# Battery_manegment.net
KiCad netlist of a schematic drawn in Altium Designer
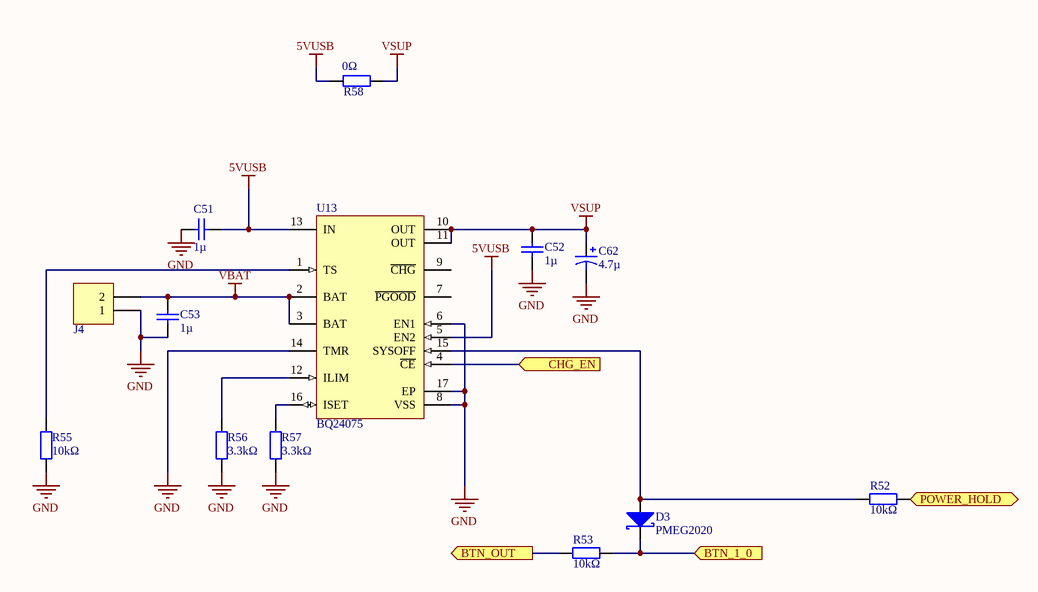
[diagram p0: Battery_manegment.SchDoc]

(export (version "E")
  (design (tool "Eeschema 10.0.6"))
  (components
    (comp (ref "C51")
      (value "1µ")
      (footprint "0603C")
      (description "ceramic X5R SMD capacitor smd 0603 1µF 50V")
      (fields (field (name "PART NUMBER") "ZSC0003") (field (name "MANUFACTURER") "Murata"))
      (libsource (lib "components") (part "Capacitor"))
    )
    (comp (ref "C52")
      (value "1µ")
      (footprint "0603C")
      (description "ceramic X5R SMD capacitor smd 0603 1µF 50V")
      (fields (field (name "PART NUMBER") "ZSC0003") (field (name "MANUFACTURER") "Murata"))
      (libsource (lib "components") (part "Capacitor"))
    )
    (comp (ref "C53")
      (value "1µ")
      (footprint "0603C")
      (description "ceramic X5R SMD capacitor smd 0603 1µF 50V")
      (fields (field (name "PART NUMBER") "ZSC0003") (field (name "MANUFACTURER") "Murata"))
      (libsource (lib "components") (part "Capacitor"))
    )
    (comp (ref "C62")
      (value "4.7µ")
      (footprint "A")
      (description "tantalum SMD capacitor 4.7µF 16V A case")
      (fields (field (name "PART NUMBER") "CST0011") (field (name "MANUFACTURER") "Kemet"))
      (libsource (lib "components") (part "Capacitor polarized"))
    )
    (comp (ref "D3")
      (value "PMEG2020")
      (footprint "SOD323")
      (description "Shotkey diode 2A 20V")
      (fields (field (name "PART NUMBER") "XDS0004") (field (name "MANUFACTURER") "Infineon"))
      (libsource (lib "components") (part "SCHOTTKY1"))
    )
    (comp (ref "J4")
      (value "B2B-PH-K-S(LF)(SN)")
      (footprint "JST_PH_2_V")
      (description "JST PH connector 2 poles vertical")
      (fields (field (name "PART NUMBER") "CJP0005") (field (name "MANUFACTURER") "JST"))
      (libsource (lib "components") (part "PH_2"))
    )
    (comp (ref "R52")
      (value "10kΩ")
      (footprint "0603R")
      (description "resistor smd 0603 10kΩ 1% 0.1w")
      (fields (field (name "PART NUMBER") "YRS0016") (field (name "MANUFACTURER") "Vishay"))
      (libsource (lib "components") (part "Resistor"))
    )
    (comp (ref "R53")
      (value "10kΩ")
      (footprint "0603R")
      (description "resistor smd 0603 10kΩ 1% 0.1w")
      (fields (field (name "PART NUMBER") "YRS0016") (field (name "MANUFACTURER") "Vishay"))
      (libsource (lib "components") (part "Resistor"))
    )
    (comp (ref "R55")
      (value "10kΩ")
      (footprint "0603R")
      (description "resistor smd 0603 10kΩ 1% 0.1w")
      (fields (field (name "PART NUMBER") "YRS0016") (field (name "MANUFACTURER") "Vishay"))
      (libsource (lib "") (part "Resistor_1"))
    )
    (comp (ref "R56")
      (value "3.3kΩ")
      (footprint "0603R")
      (description "resistor smd 0603 3.3kΩ 5% 0.1w")
      (fields (field (name "PART NUMBER") "XRS0055") (field (name "MANUFACTURER") "Yageo"))
      (libsource (lib "") (part "Resistor_1"))
    )
    (comp (ref "R57")
      (value "3.3kΩ")
      (footprint "0603R")
      (description "resistor smd 0603 3.3kΩ 5% 0.1w")
      (fields (field (name "PART NUMBER") "XRS0055") (field (name "MANUFACTURER") "Yageo"))
      (libsource (lib "") (part "Resistor_1"))
    )
    (comp (ref "R58")
      (value "0Ω")
      (footprint "0603R")
      (description "resistor smd 0603 0Ω 5% 0.1w")
      (fields (field (name "PART NUMBER") "XRS0022") (field (name "MANUFACTURER") "Panasonic"))
      (libsource (lib "") (part "Resistor_2"))
    )
    (comp (ref "U13")
      (value "BQ24075")
      (footprint "QFN16_PAD")
      (description "1.5-A USB-Friendly Li-Ion Battery Charger and Power-Path Management IC")
      (fields (field (name "PART NUMBER") "BAC0000") (field (name "MANUFACTURER") "Texas Instruments"))
      (libsource (lib "components") (part "BQ24075"))
    )
  )
  (nets
    (net (code "1") (name "/BTN_1_0") (class "Default")
      (node (ref "D3") (pin "2") (pinfunction "K_2") (pintype "passive"))
      (node (ref "R53") (pin "1") (pinfunction "1_1") (pintype "passive"))
    )
    (net (code "2") (name "/BTN_OUT") (class "Default")
      (node (ref "R53") (pin "2") (pinfunction "2_2") (pintype "passive"))
    )
    (net (code "3") (name "/CHG_EN") (class "Default")
      (node (ref "U13") (pin "4") (pinfunction "~{CE}_4") (pintype "input"))
    )
    (net (code "4") (name "/POWER_HOLD") (class "Default")
      (node (ref "R52") (pin "1") (pinfunction "1_1") (pintype "passive"))
    )
    (net (code "5") (name "5VUSB") (class "Default")
      (node (ref "C51") (pin "2") (pinfunction "2_2") (pintype "passive"))
      (node (ref "R58") (pin "1") (pinfunction "1_1") (pintype "passive"))
      (node (ref "U13") (pin "13") (pinfunction "IN_13") (pintype "power_in"))
      (node (ref "U13") (pin "5") (pinfunction "EN2_5") (pintype "input"))
    )
    (net (code "6") (name "GND") (class "Default")
      (node (ref "C51") (pin "1") (pinfunction "1_1") (pintype "passive"))
      (node (ref "C52") (pin "1") (pinfunction "1_1") (pintype "passive"))
      (node (ref "C53") (pin "1") (pinfunction "1_1") (pintype "passive"))
      (node (ref "C62") (pin "2") (pinfunction "2_2") (pintype "passive"))
      (node (ref "J4") (pin "1") (pinfunction "1_1") (pintype "passive"))
      (node (ref "R55") (pin "1") (pinfunction "1_1") (pintype "passive"))
      (node (ref "R56") (pin "1") (pinfunction "1_1") (pintype "passive"))
      (node (ref "R57") (pin "1") (pinfunction "1_1") (pintype "passive"))
      (node (ref "U13") (pin "14") (pinfunction "TMR_14") (pintype "passive"))
      (node (ref "U13") (pin "17") (pinfunction "EP_17") (pintype "power_in"))
      (node (ref "U13") (pin "6") (pinfunction "EN1_6") (pintype "input"))
      (node (ref "U13") (pin "8") (pinfunction "VSS_8") (pintype "power_in"))
    )
    (net (code "7") (name "Net-(D3-A)") (class "Default")
      (node (ref "D3") (pin "1") (pinfunction "A_1") (pintype "passive"))
      (node (ref "R52") (pin "2") (pinfunction "2_2") (pintype "passive"))
      (node (ref "U13") (pin "15") (pinfunction "SYSOFF_15") (pintype "input"))
    )
    (net (code "8") (name "Net-(U13-ILIM)") (class "Default")
      (node (ref "R56") (pin "2") (pinfunction "2_2") (pintype "passive"))
      (node (ref "U13") (pin "12") (pinfunction "ILIM_12") (pintype "input"))
    )
    (net (code "9") (name "Net-(U13-ISET)") (class "Default")
      (node (ref "R57") (pin "2") (pinfunction "2_2") (pintype "passive"))
      (node (ref "U13") (pin "16") (pinfunction "ISET_16") (pintype "bidirectional"))
    )
    (net (code "10") (name "Net-(U13-TS)") (class "Default")
      (node (ref "R55") (pin "2") (pinfunction "2_2") (pintype "passive"))
      (node (ref "U13") (pin "1") (pinfunction "TS_1") (pintype "input"))
    )
    (net (code "11") (name "VBAT") (class "Default")
      (node (ref "C53") (pin "2") (pinfunction "2_2") (pintype "passive"))
      (node (ref "J4") (pin "2") (pinfunction "2_2") (pintype "passive"))
      (node (ref "U13") (pin "2") (pinfunction "BAT_2") (pintype "power_in"))
      (node (ref "U13") (pin "3") (pinfunction "BAT_3") (pintype "power_in"))
    )
    (net (code "12") (name "VSUP") (class "Default")
      (node (ref "C52") (pin "2") (pinfunction "2_2") (pintype "passive"))
      (node (ref "C62") (pin "1") (pinfunction "1_1") (pintype "passive"))
      (node (ref "R58") (pin "2") (pinfunction "2_2") (pintype "passive"))
      (node (ref "U13") (pin "10") (pinfunction "OUT_10") (pintype "power_in"))
      (node (ref "U13") (pin "11") (pinfunction "OUT_11") (pintype "power_in"))
    )
    (net (code "13") (name "unconnected-(U13-~{CHG}-Pad9)") (class "Default")
      (node (ref "U13") (pin "9") (pinfunction "~{CHG}_9") (pintype "tri_state"))
    )
    (net (code "14") (name "unconnected-(U13-~{PGOOD}-Pad7)") (class "Default")
      (node (ref "U13") (pin "7") (pinfunction "~{PGOOD}_7") (pintype "tri_state"))
    )
  )
)
